# Robotics_Booster_Pack.net
KiCad netlist of a schematic drawn in EAGLE
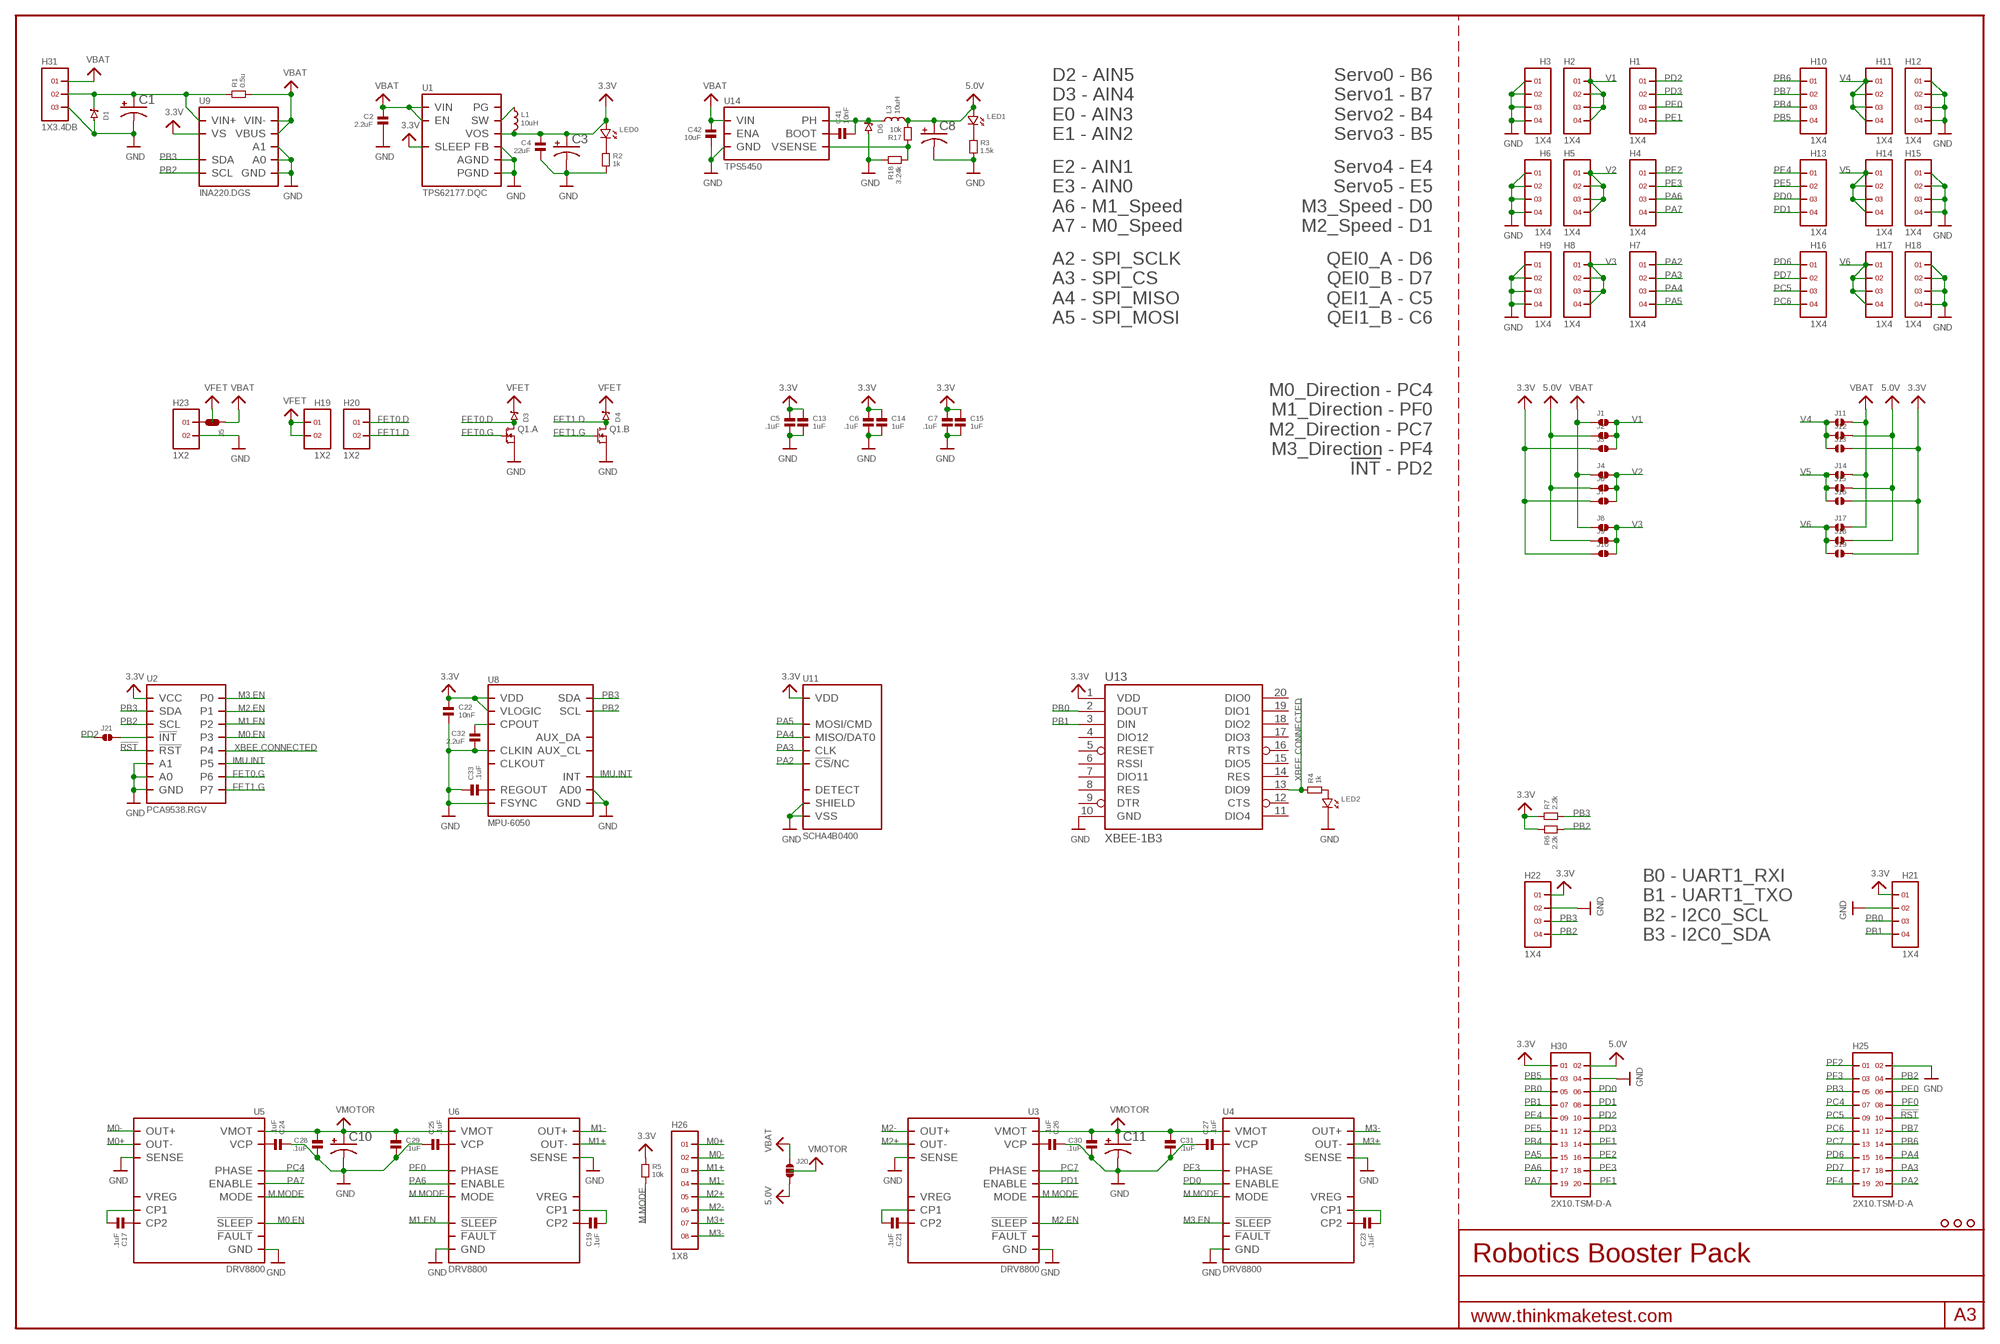
[diagram p0: schematic, sheet 1]

(export (version "E")
  (design (tool "Eeschema 10.0.6"))
  (components
    (comp (ref "C1")
      (value "CPOL-USE")
      (footprint "eagle-import:PANASONIC_E")
      (libsource (lib "eagle-import") (part "CPOL-USE"))
    )
    (comp (ref "C2")
      (value "2.2uF")
      (footprint "eagle-import:0603")
      (libsource (lib "eagle-import") (part "CAPACITOR.0603"))
    )
    (comp (ref "C3")
      (value "CPOL-USE")
      (footprint "eagle-import:PANASONIC_E")
      (libsource (lib "eagle-import") (part "CPOL-USE"))
    )
    (comp (ref "C4")
      (value "22uF")
      (footprint "eagle-import:0805")
      (libsource (lib "eagle-import") (part "CAPACITOR.0805"))
    )
    (comp (ref "C5")
      (value ".1uF")
      (footprint "eagle-import:0603")
      (libsource (lib "eagle-import") (part "CAPACITOR.0603"))
    )
    (comp (ref "C6")
      (value ".1uF")
      (footprint "eagle-import:0603")
      (libsource (lib "eagle-import") (part "CAPACITOR.0603"))
    )
    (comp (ref "C7")
      (value ".1uF")
      (footprint "eagle-import:0603")
      (libsource (lib "eagle-import") (part "CAPACITOR.0603"))
    )
    (comp (ref "C8")
      (value "CPOL-USE")
      (footprint "eagle-import:PANASONIC_E")
      (libsource (lib "eagle-import") (part "CPOL-USE"))
    )
    (comp (ref "C10")
      (value "CPOL-USE")
      (footprint "eagle-import:PANASONIC_E")
      (libsource (lib "eagle-import") (part "CPOL-USE"))
    )
    (comp (ref "C11")
      (value "CPOL-USE")
      (footprint "eagle-import:PANASONIC_E")
      (libsource (lib "eagle-import") (part "CPOL-USE"))
    )
    (comp (ref "C13")
      (value "1uF")
      (footprint "eagle-import:0603")
      (libsource (lib "eagle-import") (part "CAPACITOR.0603"))
    )
    (comp (ref "C14")
      (value "1uF")
      (footprint "eagle-import:0603")
      (libsource (lib "eagle-import") (part "CAPACITOR.0603"))
    )
    (comp (ref "C15")
      (value "1uF")
      (footprint "eagle-import:0603")
      (libsource (lib "eagle-import") (part "CAPACITOR.0603"))
    )
    (comp (ref "C17")
      (value ".1uF")
      (footprint "eagle-import:0603")
      (libsource (lib "eagle-import") (part "CAPACITOR.0603"))
    )
    (comp (ref "C19")
      (value ".1uF")
      (footprint "eagle-import:0603")
      (libsource (lib "eagle-import") (part "CAPACITOR.0603"))
    )
    (comp (ref "C21")
      (value ".1uF")
      (footprint "eagle-import:0603")
      (libsource (lib "eagle-import") (part "CAPACITOR.0603"))
    )
    (comp (ref "C22")
      (value "10nF")
      (footprint "eagle-import:0603")
      (libsource (lib "eagle-import") (part "CAPACITOR.0603"))
    )
    (comp (ref "C23")
      (value ".1uF")
      (footprint "eagle-import:0603")
      (libsource (lib "eagle-import") (part "CAPACITOR.0603"))
    )
    (comp (ref "C24")
      (value ".1uF")
      (footprint "eagle-import:0603")
      (libsource (lib "eagle-import") (part "CAPACITOR.0603"))
    )
    (comp (ref "C25")
      (value ".1uF")
      (footprint "eagle-import:0603")
      (libsource (lib "eagle-import") (part "CAPACITOR.0603"))
    )
    (comp (ref "C26")
      (value ".1uF")
      (footprint "eagle-import:0603")
      (libsource (lib "eagle-import") (part "CAPACITOR.0603"))
    )
    (comp (ref "C27")
      (value ".1uF")
      (footprint "eagle-import:0603")
      (libsource (lib "eagle-import") (part "CAPACITOR.0603"))
    )
    (comp (ref "C28")
      (value ".1uF")
      (footprint "eagle-import:0603")
      (libsource (lib "eagle-import") (part "CAPACITOR.0603"))
    )
    (comp (ref "C29")
      (value ".1uF")
      (footprint "eagle-import:0603")
      (libsource (lib "eagle-import") (part "CAPACITOR.0603"))
    )
    (comp (ref "C30")
      (value ".1uF")
      (footprint "eagle-import:0603")
      (libsource (lib "eagle-import") (part "CAPACITOR.0603"))
    )
    (comp (ref "C31")
      (value ".1uF")
      (footprint "eagle-import:0603")
      (libsource (lib "eagle-import") (part "CAPACITOR.0603"))
    )
    (comp (ref "C32")
      (value "2.2uF")
      (footprint "eagle-import:0603")
      (libsource (lib "eagle-import") (part "CAPACITOR.0603"))
    )
    (comp (ref "C33")
      (value ".1uF")
      (footprint "eagle-import:0603")
      (libsource (lib "eagle-import") (part "CAPACITOR.0603"))
    )
    (comp (ref "C41")
      (value "10nF")
      (footprint "eagle-import:0603")
      (libsource (lib "eagle-import") (part "CAPACITOR.0603"))
    )
    (comp (ref "C42")
      (value "10uF")
      (footprint "eagle-import:1206")
      (libsource (lib "eagle-import") (part "CAPACITOR.1206"))
    )
    (comp (ref "D1")
      (value "CDBMT2100-HF")
      (footprint "eagle-import:SOD-123H")
      (libsource (lib "eagle-import") (part "CDBMT____-HF"))
    )
    (comp (ref "D3")
      (value "CDBMT2100-HF")
      (footprint "eagle-import:SOD-123H")
      (libsource (lib "eagle-import") (part "CDBMT____-HF"))
    )
    (comp (ref "D4")
      (value "CDBMT2100-HF")
      (footprint "eagle-import:SOD-123H")
      (libsource (lib "eagle-import") (part "CDBMT____-HF"))
    )
    (comp (ref "D6")
      (value "CDBC5XXX-G")
      (footprint "eagle-import:DO-214AB")
      (libsource (lib "eagle-import") (part "CDBC5XXX-G"))
    )
    (comp (ref "H1")
      (value "1X4")
      (footprint "eagle-import:1X4")
      (libsource (lib "eagle-import") (part "1X4"))
    )
    (comp (ref "H2")
      (value "1X4")
      (footprint "eagle-import:1X4")
      (libsource (lib "eagle-import") (part "1X4"))
    )
    (comp (ref "H3")
      (value "1X4")
      (footprint "eagle-import:1X4")
      (libsource (lib "eagle-import") (part "1X4"))
    )
    (comp (ref "H4")
      (value "1X4")
      (footprint "eagle-import:1X4")
      (libsource (lib "eagle-import") (part "1X4"))
    )
    (comp (ref "H5")
      (value "1X4")
      (footprint "eagle-import:1X4")
      (libsource (lib "eagle-import") (part "1X4"))
    )
    (comp (ref "H6")
      (value "1X4")
      (footprint "eagle-import:1X4")
      (libsource (lib "eagle-import") (part "1X4"))
    )
    (comp (ref "H7")
      (value "1X4")
      (footprint "eagle-import:1X4")
      (libsource (lib "eagle-import") (part "1X4"))
    )
    (comp (ref "H8")
      (value "1X4")
      (footprint "eagle-import:1X4")
      (libsource (lib "eagle-import") (part "1X4"))
    )
    (comp (ref "H9")
      (value "1X4")
      (footprint "eagle-import:1X4")
      (libsource (lib "eagle-import") (part "1X4"))
    )
    (comp (ref "H10")
      (value "1X4")
      (footprint "eagle-import:1X4")
      (libsource (lib "eagle-import") (part "1X4"))
    )
    (comp (ref "H11")
      (value "1X4")
      (footprint "eagle-import:1X4")
      (libsource (lib "eagle-import") (part "1X4"))
    )
    (comp (ref "H12")
      (value "1X4")
      (footprint "eagle-import:1X4")
      (libsource (lib "eagle-import") (part "1X4"))
    )
    (comp (ref "H13")
      (value "1X4")
      (footprint "eagle-import:1X4")
      (libsource (lib "eagle-import") (part "1X4"))
    )
    (comp (ref "H14")
      (value "1X4")
      (footprint "eagle-import:1X4")
      (libsource (lib "eagle-import") (part "1X4"))
    )
    (comp (ref "H15")
      (value "1X4")
      (footprint "eagle-import:1X4")
      (libsource (lib "eagle-import") (part "1X4"))
    )
    (comp (ref "H16")
      (value "1X4")
      (footprint "eagle-import:1X4")
      (libsource (lib "eagle-import") (part "1X4"))
    )
    (comp (ref "H17")
      (value "1X4")
      (footprint "eagle-import:1X4")
      (libsource (lib "eagle-import") (part "1X4"))
    )
    (comp (ref "H18")
      (value "1X4")
      (footprint "eagle-import:1X4")
      (libsource (lib "eagle-import") (part "1X4"))
    )
    (comp (ref "H19")
      (value "1X2")
      (footprint "eagle-import:1X2")
      (libsource (lib "eagle-import") (part "1X2"))
    )
    (comp (ref "H20")
      (value "1X2")
      (footprint "eagle-import:1X2")
      (libsource (lib "eagle-import") (part "1X2"))
    )
    (comp (ref "H21")
      (value "1X4")
      (footprint "eagle-import:1X4")
      (libsource (lib "eagle-import") (part "1X4"))
    )
    (comp (ref "H22")
      (value "1X4")
      (footprint "eagle-import:1X4")
      (libsource (lib "eagle-import") (part "1X4"))
    )
    (comp (ref "H23")
      (value "1X2")
      (footprint "eagle-import:1X2")
      (libsource (lib "eagle-import") (part "1X2"))
    )
    (comp (ref "H25")
      (value "2X10.TSM-D-A")
      (footprint "eagle-import:TSM-110-XX-XXX-DV-A")
      (libsource (lib "eagle-import") (part "2X10.TSM-D-A"))
    )
    (comp (ref "H26")
      (value "1X8")
      (footprint "eagle-import:1824480000")
      (libsource (lib "eagle-import") (part "1X8"))
    )
    (comp (ref "H30")
      (value "2X10.TSM-D-A")
      (footprint "eagle-import:TSM-110-XX-XXX-DV-A")
      (libsource (lib "eagle-import") (part "2X10.TSM-D-A"))
    )
    (comp (ref "H31")
      (value "1X3.4DB")
      (footprint "eagle-import:4DB-P108-02")
      (libsource (lib "eagle-import") (part "1X3.4DB"))
    )
    (comp (ref "J1")
      (value "SOLDERJUMPER.2.LRG")
      (footprint "eagle-import:2.LRG")
      (libsource (lib "eagle-import") (part "SOLDERJUMPER.2.LRG"))
    )
    (comp (ref "J2")
      (value "SOLDERJUMPER.2.LRG")
      (footprint "eagle-import:2.LRG")
      (libsource (lib "eagle-import") (part "SOLDERJUMPER.2.LRG"))
    )
    (comp (ref "J3")
      (value "SOLDERJUMPER.2.LRG.PASTE")
      (footprint "eagle-import:2.LRG.PASTE")
      (libsource (lib "eagle-import") (part "SOLDERJUMPER.2.LRG.PASTE"))
    )
    (comp (ref "J4")
      (value "SOLDERJUMPER.2.LRG")
      (footprint "eagle-import:2.LRG")
      (libsource (lib "eagle-import") (part "SOLDERJUMPER.2.LRG"))
    )
    (comp (ref "J5")
      (value "SOLDERJUMPER.3.LRG.12")
      (footprint "eagle-import:3.LRG.12")
      (libsource (lib "eagle-import") (part "SOLDERJUMPER.3.LRG.12"))
    )
    (comp (ref "J6")
      (value "SOLDERJUMPER.2.LRG")
      (footprint "eagle-import:2.LRG")
      (libsource (lib "eagle-import") (part "SOLDERJUMPER.2.LRG"))
    )
    (comp (ref "J7")
      (value "SOLDERJUMPER.2.LRG.PASTE")
      (footprint "eagle-import:2.LRG.PASTE")
      (libsource (lib "eagle-import") (part "SOLDERJUMPER.2.LRG.PASTE"))
    )
    (comp (ref "J8")
      (value "SOLDERJUMPER.2.LRG")
      (footprint "eagle-import:2.LRG")
      (libsource (lib "eagle-import") (part "SOLDERJUMPER.2.LRG"))
    )
    (comp (ref "J9")
      (value "SOLDERJUMPER.2.LRG")
      (footprint "eagle-import:2.LRG")
      (libsource (lib "eagle-import") (part "SOLDERJUMPER.2.LRG"))
    )
    (comp (ref "J10")
      (value "SOLDERJUMPER.2.LRG.PASTE")
      (footprint "eagle-import:2.LRG.PASTE")
      (libsource (lib "eagle-import") (part "SOLDERJUMPER.2.LRG.PASTE"))
    )
    (comp (ref "J11")
      (value "SOLDERJUMPER.2.LRG")
      (footprint "eagle-import:2.LRG")
      (libsource (lib "eagle-import") (part "SOLDERJUMPER.2.LRG"))
    )
    (comp (ref "J12")
      (value "SOLDERJUMPER.2.LRG.PASTE")
      (footprint "eagle-import:2.LRG.PASTE")
      (libsource (lib "eagle-import") (part "SOLDERJUMPER.2.LRG.PASTE"))
    )
    (comp (ref "J13")
      (value "SOLDERJUMPER.2.LRG")
      (footprint "eagle-import:2.LRG")
      (libsource (lib "eagle-import") (part "SOLDERJUMPER.2.LRG"))
    )
    (comp (ref "J14")
      (value "SOLDERJUMPER.2.LRG")
      (footprint "eagle-import:2.LRG")
      (libsource (lib "eagle-import") (part "SOLDERJUMPER.2.LRG"))
    )
    (comp (ref "J15")
      (value "SOLDERJUMPER.2.LRG")
      (footprint "eagle-import:2.LRG")
      (libsource (lib "eagle-import") (part "SOLDERJUMPER.2.LRG"))
    )
    (comp (ref "J16")
      (value "SOLDERJUMPER.2.LRG.PASTE")
      (footprint "eagle-import:2.LRG.PASTE")
      (libsource (lib "eagle-import") (part "SOLDERJUMPER.2.LRG.PASTE"))
    )
    (comp (ref "J17")
      (value "SOLDERJUMPER.2.LRG")
      (footprint "eagle-import:2.LRG")
      (libsource (lib "eagle-import") (part "SOLDERJUMPER.2.LRG"))
    )
    (comp (ref "J18")
      (value "SOLDERJUMPER.2.LRG")
      (footprint "eagle-import:2.LRG")
      (libsource (lib "eagle-import") (part "SOLDERJUMPER.2.LRG"))
    )
    (comp (ref "J19")
      (value "SOLDERJUMPER.2.LRG.PASTE")
      (footprint "eagle-import:2.LRG.PASTE")
      (libsource (lib "eagle-import") (part "SOLDERJUMPER.2.LRG.PASTE"))
    )
    (comp (ref "J20")
      (value "SOLDERJUMPER.3.LRG.12")
      (footprint "eagle-import:3.LRG.12")
      (libsource (lib "eagle-import") (part "SOLDERJUMPER.3.LRG.12"))
    )
    (comp (ref "J21")
      (value "SOLDERJUMPER.2.LRG")
      (footprint "eagle-import:2.LRG")
      (libsource (lib "eagle-import") (part "SOLDERJUMPER.2.LRG"))
    )
    (comp (ref "L1")
      (value "10uH")
      (footprint "eagle-import:SRN6045")
      (libsource (lib "eagle-import") (part "INDUCTOR-SRN6045"))
    )
    (comp (ref "L3")
      (value "10uH")
      (footprint "eagle-import:XAL6060")
      (libsource (lib "eagle-import") (part "INDUCTOR.XAL6060"))
    )
    (comp (ref "LED0")
      (value "LED.0603")
      (footprint "eagle-import:0603.LED")
      (libsource (lib "eagle-import") (part "LED.0603"))
    )
    (comp (ref "LED1")
      (value "LED.0603")
      (footprint "eagle-import:0603.LED")
      (libsource (lib "eagle-import") (part "LED.0603"))
    )
    (comp (ref "LED2")
      (value "LED.0603")
      (footprint "eagle-import:0603.LED")
      (libsource (lib "eagle-import") (part "LED.0603"))
    )
    (comp (ref "Q1")
      (value "FDMA")
      (footprint "eagle-import:MICROFET.2X2")
      (libsource (lib "eagle-import") (part "FDMA"))
    )
    (comp (ref "R1")
      (value "0.5u")
      (footprint "eagle-import:2512")
      (libsource (lib "eagle-import") (part "RESISTOR.2512"))
    )
    (comp (ref "R2")
      (value "1k")
      (footprint "eagle-import:0603")
      (libsource (lib "eagle-import") (part "RESISTOR.0603"))
    )
    (comp (ref "R3")
      (value "1.5k")
      (footprint "eagle-import:0603")
      (libsource (lib "eagle-import") (part "RESISTOR.0603"))
    )
    (comp (ref "R4")
      (value "1k")
      (footprint "eagle-import:0603")
      (libsource (lib "eagle-import") (part "RESISTOR.0603"))
    )
    (comp (ref "R5")
      (value "10k")
      (footprint "eagle-import:0603")
      (libsource (lib "eagle-import") (part "RESISTOR.0603"))
    )
    (comp (ref "R6")
      (value "2.2k")
      (footprint "eagle-import:0603")
      (libsource (lib "eagle-import") (part "RESISTOR.0603"))
    )
    (comp (ref "R7")
      (value "2.2k")
      (footprint "eagle-import:0603")
      (libsource (lib "eagle-import") (part "RESISTOR.0603"))
    )
    (comp (ref "R17")
      (value "10k")
      (footprint "eagle-import:0603")
      (libsource (lib "eagle-import") (part "RESISTOR.0603"))
    )
    (comp (ref "R18")
      (value "3.24k")
      (footprint "eagle-import:0603")
      (libsource (lib "eagle-import") (part "RESISTOR.0603"))
    )
    (comp (ref "U$3")
      (value "HOLE.4MM")
      (footprint "eagle-import:#4")
      (libsource (lib "eagle-import") (part "HOLE.4MM"))
    )
    (comp (ref "U$4")
      (value "HOLE.4MM")
      (footprint "eagle-import:#4")
      (libsource (lib "eagle-import") (part "HOLE.4MM"))
    )
    (comp (ref "U$21")
      (value "HOLE.4MM")
      (footprint "eagle-import:#4")
      (libsource (lib "eagle-import") (part "HOLE.4MM"))
    )
    (comp (ref "U1")
      (value "TPS62177.DQC")
      (footprint "eagle-import:DQC")
      (libsource (lib "eagle-import") (part "TPS62177.DQC"))
    )
    (comp (ref "U2")
      (value "PCA9538.RGV")
      (footprint "eagle-import:RGV.16")
      (libsource (lib "eagle-import") (part "PCA9538.RGV"))
    )
    (comp (ref "U3")
      (value "DRV8800")
      (footprint "eagle-import:RTY.16")
      (libsource (lib "eagle-import") (part "DRV8800.RTY"))
    )
    (comp (ref "U4")
      (value "DRV8800")
      (footprint "eagle-import:RTY.16")
      (libsource (lib "eagle-import") (part "DRV8800.RTY"))
    )
    (comp (ref "U5")
      (value "DRV8800")
      (footprint "eagle-import:RTY.16")
      (libsource (lib "eagle-import") (part "DRV8800.RTY"))
    )
    (comp (ref "U6")
      (value "DRV8800")
      (footprint "eagle-import:RTY.16")
      (libsource (lib "eagle-import") (part "DRV8800.RTY"))
    )
    (comp (ref "U8")
      (value "MPU-6050")
      (footprint "eagle-import:QFN.24.4X4")
      (libsource (lib "eagle-import") (part "MPU-6050"))
    )
    (comp (ref "U9")
      (value "INA220.DGS")
      (footprint "eagle-import:DGS.10")
      (libsource (lib "eagle-import") (part "INA220.DGS"))
    )
    (comp (ref "U11")
      (value "SCHA4B0400")
      (footprint "eagle-import:SCHA4B0400")
      (libsource (lib "eagle-import") (part "SCHA4B0400"))
    )
    (comp (ref "U13")
      (value "XBEE-1B3")
      (footprint "eagle-import:XBEE-SMD")
      (libsource (lib "eagle-import") (part "XBEE-1B3"))
    )
    (comp (ref "U14")
      (value "TPS5450")
      (footprint "eagle-import:DDA")
      (libsource (lib "eagle-import") (part "TPS54X0"))
    )
  )
  (nets
    (net (code "1") (name "/FET0.D") (class "Default")
      (node (ref "D3") (pin "2") (pinfunction "2_2") (pintype "bidirectional"))
      (node (ref "H20") (pin "1") (pinfunction "1_1") (pintype "bidirectional"))
      (node (ref "Q1") (pin "6") (pinfunction "D_6") (pintype "bidirectional"))
      (node (ref "Q1") (pin "PAD@1") (pinfunction "D_PAD@1") (pintype "bidirectional"))
    )
    (net (code "2") (name "/FET0.G") (class "Default")
      (node (ref "Q1") (pin "2") (pinfunction "G_2") (pintype "bidirectional"))
      (node (ref "U2") (pin "9") (pinfunction "P6_9") (pintype "bidirectional"))
    )
    (net (code "3") (name "/FET1.D") (class "Default")
      (node (ref "D4") (pin "2") (pinfunction "2_2") (pintype "bidirectional"))
      (node (ref "H20") (pin "2") (pinfunction "2_2") (pintype "bidirectional"))
      (node (ref "Q1") (pin "3") (pinfunction "D_3") (pintype "bidirectional"))
      (node (ref "Q1") (pin "PAD@2") (pinfunction "D_PAD@2") (pintype "bidirectional"))
    )
    (net (code "4") (name "/FET1.G") (class "Default")
      (node (ref "Q1") (pin "5") (pinfunction "G_5") (pintype "bidirectional"))
      (node (ref "U2") (pin "10") (pinfunction "P7_10") (pintype "bidirectional"))
    )
    (net (code "5") (name "/IMU.INT") (class "Default")
      (node (ref "U2") (pin "8") (pinfunction "P5_8") (pintype "bidirectional"))
      (node (ref "U8") (pin "12") (pinfunction "INT_12") (pintype "bidirectional"))
    )
    (net (code "6") (name "/M.MODE") (class "Default")
      (node (ref "R5") (pin "2") (pinfunction "2_2") (pintype "bidirectional"))
      (node (ref "U3") (pin "16") (pinfunction "MODE_16") (pintype "bidirectional"))
      (node (ref "U4") (pin "16") (pinfunction "MODE_16") (pintype "bidirectional"))
      (node (ref "U5") (pin "16") (pinfunction "MODE_16") (pintype "bidirectional"))
      (node (ref "U6") (pin "16") (pinfunction "MODE_16") (pintype "bidirectional"))
    )
    (net (code "7") (name "/M0+") (class "Default")
      (node (ref "H26") (pin "1@1") (pinfunction "1_1@1") (pintype "bidirectional"))
      (node (ref "H26") (pin "1@2") (pinfunction "1_1@2") (pintype "bidirectional"))
      (node (ref "U5") (pin "9") (pinfunction "OUT-_9") (pintype "bidirectional"))
    )
    (net (code "8") (name "/M0-") (class "Default")
      (node (ref "H26") (pin "2@1") (pinfunction "2_2@1") (pintype "bidirectional"))
      (node (ref "H26") (pin "2@2") (pinfunction "2_2@2") (pintype "bidirectional"))
      (node (ref "U5") (pin "6") (pinfunction "OUT+_6") (pintype "bidirectional"))
    )
    (net (code "9") (name "/M0.EN") (class "Default")
      (node (ref "U2") (pin "5") (pinfunction "P3_5") (pintype "bidirectional"))
      (node (ref "U5") (pin "3") (pinfunction "~{SLEEP}_3") (pintype "bidirectional"))
    )
    (net (code "10") (name "/M1+") (class "Default")
      (node (ref "H26") (pin "3@1") (pinfunction "3_3@1") (pintype "bidirectional"))
      (node (ref "H26") (pin "3@2") (pinfunction "3_3@2") (pintype "bidirectional"))
      (node (ref "U6") (pin "9") (pinfunction "OUT-_9") (pintype "bidirectional"))
    )
    (net (code "11") (name "/M1-") (class "Default")
      (node (ref "H26") (pin "4@1") (pinfunction "4_4@1") (pintype "bidirectional"))
      (node (ref "H26") (pin "4@2") (pinfunction "4_4@2") (pintype "bidirectional"))
      (node (ref "U6") (pin "6") (pinfunction "OUT+_6") (pintype "bidirectional"))
    )
    (net (code "12") (name "/M1.EN") (class "Default")
      (node (ref "U2") (pin "4") (pinfunction "P2_4") (pintype "bidirectional"))
      (node (ref "U6") (pin "3") (pinfunction "~{SLEEP}_3") (pintype "bidirectional"))
    )
    (net (code "13") (name "/M2+") (class "Default")
      (node (ref "H26") (pin "5@1") (pinfunction "5_5@1") (pintype "bidirectional"))
      (node (ref "H26") (pin "5@2") (pinfunction "5_5@2") (pintype "bidirectional"))
      (node (ref "U3") (pin "9") (pinfunction "OUT-_9") (pintype "bidirectional"))
    )
    (net (code "14") (name "/M2-") (class "Default")
      (node (ref "H26") (pin "6@1") (pinfunction "6_6@1") (pintype "bidirectional"))
      (node (ref "H26") (pin "6@2") (pinfunction "6_6@2") (pintype "bidirectional"))
      (node (ref "U3") (pin "6") (pinfunction "OUT+_6") (pintype "bidirectional"))
    )
    (net (code "15") (name "/M2.EN") (class "Default")
      (node (ref "U2") (pin "3") (pinfunction "P1_3") (pintype "bidirectional"))
      (node (ref "U3") (pin "3") (pinfunction "~{SLEEP}_3") (pintype "bidirectional"))
    )
    (net (code "16") (name "/M3+") (class "Default")
      (node (ref "H26") (pin "7@1") (pinfunction "7_7@1") (pintype "bidirectional"))
      (node (ref "H26") (pin "7@2") (pinfunction "7_7@2") (pintype "bidirectional"))
      (node (ref "U4") (pin "9") (pinfunction "OUT-_9") (pintype "bidirectional"))
    )
    (net (code "17") (name "/M3-") (class "Default")
      (node (ref "H26") (pin "8@1") (pinfunction "8_8@1") (pintype "bidirectional"))
      (node (ref "H26") (pin "8@2") (pinfunction "8_8@2") (pintype "bidirectional"))
      (node (ref "U4") (pin "6") (pinfunction "OUT+_6") (pintype "bidirectional"))
    )
    (net (code "18") (name "/M3.EN") (class "Default")
      (node (ref "U2") (pin "2") (pinfunction "P0_2") (pintype "bidirectional"))
      (node (ref "U4") (pin "3") (pinfunction "~{SLEEP}_3") (pintype "bidirectional"))
    )
    (net (code "19") (name "/PA2") (class "Default")
      (node (ref "H25") (pin "20") (pinfunction "20_20") (pintype "bidirectional"))
      (node (ref "H7") (pin "1") (pinfunction "1_1") (pintype "bidirectional"))
      (node (ref "U11") (pin "!CS!/NC/DAT3") (pinfunction "~{CS}/NC_!CS!/NC/DAT3") (pintype "bidirectional"))
    )
    (net (code "20") (name "/PA3") (class "Default")
      (node (ref "H25") (pin "18") (pinfunction "18_18") (pintype "bidirectional"))
      (node (ref "H7") (pin "2") (pinfunction "2_2") (pintype "bidirectional"))
      (node (ref "U11") (pin "CLK") (pinfunction "CLK_CLK") (pintype "bidirectional"))
    )
    (net (code "21") (name "/PA4") (class "Default")
      (node (ref "H25") (pin "16") (pinfunction "16_16") (pintype "bidirectional"))
      (node (ref "H7") (pin "3") (pinfunction "3_3") (pintype "bidirectional"))
      (node (ref "U11") (pin "MISO/DAT0") (pinfunction "MISO/DAT0_MISO/DAT0") (pintype "bidirectional"))
    )
    (net (code "22") (name "/PA5") (class "Default")
      (node (ref "H30") (pin "15") (pinfunction "15_15") (pintype "bidirectional"))
      (node (ref "H7") (pin "4") (pinfunction "4_4") (pintype "bidirectional"))
      (node (ref "U11") (pin "MOSI/CMD") (pinfunction "MOSI/CMD_MOSI/CMD") (pintype "bidirectional"))
    )
    (net (code "23") (name "/PA6") (class "Default")
      (node (ref "H30") (pin "17") (pinfunction "17_17") (pintype "bidirectional"))
      (node (ref "H4") (pin "3") (pinfunction "3_3") (pintype "bidirectional"))
      (node (ref "U6") (pin "4") (pinfunction "ENABLE_4") (pintype "bidirectional"))
    )
    (net (code "24") (name "/PA7") (class "Default")
      (node (ref "H30") (pin "19") (pinfunction "19_19") (pintype "bidirectional"))
      (node (ref "H4") (pin "4") (pinfunction "4_4") (pintype "bidirectional"))
      (node (ref "U5") (pin "4") (pinfunction "ENABLE_4") (pintype "bidirectional"))
    )
    (net (code "25") (name "/PB0") (class "Default")
      (node (ref "H21") (pin "3") (pinfunction "3_3") (pintype "bidirectional"))
      (node (ref "H30") (pin "5") (pinfunction "5_5") (pintype "bidirectional"))
      (node (ref "U13") (pin "2") (pinfunction "DOUT_2") (pintype "output"))
    )
    (net (code "26") (name "/PB1") (class "Default")
      (node (ref "H21") (pin "4") (pinfunction "4_4") (pintype "bidirectional"))
      (node (ref "H30") (pin "7") (pinfunction "7_7") (pintype "bidirectional"))
      (node (ref "U13") (pin "3") (pinfunction "DIN_3") (pintype "input"))
    )
    (net (code "27") (name "/PB2") (class "Default")
      (node (ref "H22") (pin "4") (pinfunction "4_4") (pintype "bidirectional"))
      (node (ref "H25") (pin "4") (pinfunction "4_4") (pintype "bidirectional"))
      (node (ref "R6") (pin "2") (pinfunction "2_2") (pintype "bidirectional"))
      (node (ref "U2") (pin "12") (pinfunction "SCL_12") (pintype "bidirectional"))
      (node (ref "U8") (pin "23") (pinfunction "SCL_23") (pintype "bidirectional"))
      (node (ref "U9") (pin "5") (pinfunction "SCL_5") (pintype "bidirectional"))
    )
    (net (code "28") (name "/PB3") (class "Default")
      (node (ref "H22") (pin "3") (pinfunction "3_3") (pintype "bidirectional"))
      (node (ref "H25") (pin "5") (pinfunction "5_5") (pintype "bidirectional"))
      (node (ref "R7") (pin "2") (pinfunction "2_2") (pintype "bidirectional"))
      (node (ref "U2") (pin "13") (pinfunction "SDA_13") (pintype "bidirectional"))
      (node (ref "U8") (pin "24") (pinfunction "SDA_24") (pintype "bidirectional"))
      (node (ref "U9") (pin "4") (pinfunction "SDA_4") (pintype "bidirectional"))
    )
    (net (code "29") (name "/PB4") (class "Default")
      (node (ref "H10") (pin "3") (pinfunction "3_3") (pintype "bidirectional"))
      (node (ref "H30") (pin "13") (pinfunction "13_13") (pintype "bidirectional"))
    )
    (net (code "30") (name "/PB5") (class "Default")
      (node (ref "H10") (pin "4") (pinfunction "4_4") (pintype "bidirectional"))
      (node (ref "H30") (pin "3") (pinfunction "3_3") (pintype "bidirectional"))
    )
    (net (code "31") (name "/PB6") (class "Default")
      (node (ref "H10") (pin "1") (pinfunction "1_1") (pintype "bidirectional"))
      (node (ref "H25") (pin "14") (pinfunction "14_14") (pintype "bidirectional"))
    )
    (net (code "32") (name "/PB7") (class "Default")
      (node (ref "H10") (pin "2") (pinfunction "2_2") (pintype "bidirectional"))
      (node (ref "H25") (pin "12") (pinfunction "12_12") (pintype "bidirectional"))
    )
    (net (code "33") (name "/PC4") (class "Default")
      (node (ref "H25") (pin "7") (pinfunction "7_7") (pintype "bidirectional"))
      (node (ref "U5") (pin "1") (pinfunction "PHASE_1") (pintype "bidirectional"))
    )
    (net (code "34") (name "/PC5") (class "Default")
      (node (ref "H16") (pin "3") (pinfunction "3_3") (pintype "bidirectional"))
      (node (ref "H25") (pin "9") (pinfunction "9_9") (pintype "bidirectional"))
    )
    (net (code "35") (name "/PC6") (class "Default")
      (node (ref "H16") (pin "4") (pinfunction "4_4") (pintype "bidirectional"))
      (node (ref "H25") (pin "11") (pinfunction "11_11") (pintype "bidirectional"))
    )
    (net (code "36") (name "/PC7") (class "Default")
      (node (ref "H25") (pin "13") (pinfunction "13_13") (pintype "bidirectional"))
      (node (ref "U3") (pin "1") (pinfunction "PHASE_1") (pintype "bidirectional"))
    )
    (net (code "37") (name "/PD0") (class "Default")
      (node (ref "H13") (pin "3") (pinfunction "3_3") (pintype "bidirectional"))
      (node (ref "H30") (pin "6") (pinfunction "6_6") (pintype "bidirectional"))
      (node (ref "U4") (pin "4") (pinfunction "ENABLE_4") (pintype "bidirectional"))
    )
    (net (code "38") (name "/PD1") (class "Default")
      (node (ref "H13") (pin "4") (pinfunction "4_4") (pintype "bidirectional"))
      (node (ref "H30") (pin "8") (pinfunction "8_8") (pintype "bidirectional"))
      (node (ref "U3") (pin "4") (pinfunction "ENABLE_4") (pintype "bidirectional"))
    )
    (net (code "39") (name "/PD2") (class "Default")
      (node (ref "H1") (pin "1") (pinfunction "1_1") (pintype "bidirectional"))
      (node (ref "H30") (pin "10") (pinfunction "10_10") (pintype "bidirectional"))
      (node (ref "J21") (pin "1") (pinfunction "1_1") (pintype "bidirectional"))
    )
    (net (code "40") (name "/PD3") (class "Default")
      (node (ref "H1") (pin "2") (pinfunction "2_2") (pintype "bidirectional"))
      (node (ref "H30") (pin "12") (pinfunction "12_12") (pintype "bidirectional"))
    )
    (net (code "41") (name "/PD6") (class "Default")
      (node (ref "H16") (pin "1") (pinfunction "1_1") (pintype "bidirectional"))
      (node (ref "H25") (pin "15") (pinfunction "15_15") (pintype "bidirectional"))
    )
    (net (code "42") (name "/PD7") (class "Default")
      (node (ref "H16") (pin "2") (pinfunction "2_2") (pintype "bidirectional"))
      (node (ref "H25") (pin "17") (pinfunction "17_17") (pintype "bidirectional"))
    )
    (net (code "43") (name "/PE0") (class "Default")
      (node (ref "H1") (pin "3") (pinfunction "3_3") (pintype "bidirectional"))
      (node (ref "H25") (pin "6") (pinfunction "6_6") (pintype "bidirectional"))
    )
    (net (code "44") (name "/PE1") (class "Default")
      (node (ref "H1") (pin "4") (pinfunction "4_4") (pintype "bidirectional"))
      (node (ref "H30") (pin "14") (pinfunction "14_14") (pintype "bidirectional"))
    )
    (net (code "45") (name "/PE2") (class "Default")
      (node (ref "H30") (pin "16") (pinfunction "16_16") (pintype "bidirectional"))
      (node (ref "H4") (pin "1") (pinfunction "1_1") (pintype "bidirectional"))
    )
    (net (code "46") (name "/PE3") (class "Default")
      (node (ref "H30") (pin "18") (pinfunction "18_18") (pintype "bidirectional"))
      (node (ref "H4") (pin "2") (pinfunction "2_2") (pintype "bidirectional"))
    )
    (net (code "47") (name "/PE4") (class "Default")
      (node (ref "H13") (pin "1") (pinfunction "1_1") (pintype "bidirectional"))
      (node (ref "H30") (pin "9") (pinfunction "9_9") (pintype "bidirectional"))
    )
    (net (code "48") (name "/PE5") (class "Default")
      (node (ref "H13") (pin "2") (pinfunction "2_2") (pintype "bidirectional"))
      (node (ref "H30") (pin "11") (pinfunction "11_11") (pintype "bidirectional"))
    )
    (net (code "49") (name "/PF0") (class "Default")
      (node (ref "H25") (pin "8") (pinfunction "8_8") (pintype "bidirectional"))
      (node (ref "U6") (pin "1") (pinfunction "PHASE_1") (pintype "bidirectional"))
    )
    (net (code "50") (name "/PF1") (class "Default")
      (node (ref "H30") (pin "20") (pinfunction "20_20") (pintype "bidirectional"))
    )
    (net (code "51") (name "/PF2") (class "Default")
      (node (ref "H25") (pin "1") (pinfunction "1_1") (pintype "bidirectional"))
    )
    (net (code "52") (name "/PF3") (class "Default")
      (node (ref "H25") (pin "3") (pinfunction "3_3") (pintype "bidirectional"))
      (node (ref "U4") (pin "1") (pinfunction "PHASE_1") (pintype "bidirectional"))
    )
    (net (code "53") (name "/PF4") (class "Default")
      (node (ref "H25") (pin "19") (pinfunction "19_19") (pintype "bidirectional"))
    )
    (net (code "54") (name "/V1") (class "Default")
      (node (ref "H2") (pin "1") (pinfunction "1_1") (pintype "bidirectional"))
      (node (ref "H2") (pin "2") (pinfunction "2_2") (pintype "bidirectional"))
      (node (ref "H2") (pin "3") (pinfunction "3_3") (pintype "bidirectional"))
      (node (ref "H2") (pin "4") (pinfunction "4_4") (pintype "bidirectional"))
      (node (ref "J1") (pin "2") (pinfunction "2_2") (pintype "bidirectional"))
      (node (ref "J2") (pin "2") (pinfunction "2_2") (pintype "bidirectional"))
      (node (ref "J3") (pin "2") (pinfunction "2_2") (pintype "bidirectional"))
    )
    (net (code "55") (name "/V2") (class "Default")
      (node (ref "H5") (pin "1") (pinfunction "1_1") (pintype "bidirectional"))
      (node (ref "H5") (pin "2") (pinfunction "2_2") (pintype "bidirectional"))
      (node (ref "H5") (pin "3") (pinfunction "3_3") (pintype "bidirectional"))
      (node (ref "H5") (pin "4") (pinfunction "4_4") (pintype "bidirectional"))
      (node (ref "J4") (pin "2") (pinfunction "2_2") (pintype "bidirectional"))
      (node (ref "J6") (pin "2") (pinfunction "2_2") (pintype "bidirectional"))
      (node (ref "J7") (pin "2") (pinfunction "2_2") (pintype "bidirectional"))
    )
    (net (code "56") (name "/V3") (class "Default")
      (node (ref "H8") (pin "1") (pinfunction "1_1") (pintype "bidirectional"))
      (node (ref "H8") (pin "2") (pinfunction "2_2") (pintype "bidirectional"))
      (node (ref "H8") (pin "3") (pinfunction "3_3") (pintype "bidirectional"))
      (node (ref "H8") (pin "4") (pinfunction "4_4") (pintype "bidirectional"))
      (node (ref "J10") (pin "2") (pinfunction "2_2") (pintype "bidirectional"))
      (node (ref "J8") (pin "2") (pinfunction "2_2") (pintype "bidirectional"))
      (node (ref "J9") (pin "2") (pinfunction "2_2") (pintype "bidirectional"))
    )
    (net (code "57") (name "/V4") (class "Default")
      (node (ref "H11") (pin "1") (pinfunction "1_1") (pintype "bidirectional"))
      (node (ref "H11") (pin "2") (pinfunction "2_2") (pintype "bidirectional"))
      (node (ref "H11") (pin "3") (pinfunction "3_3") (pintype "bidirectional"))
      (node (ref "H11") (pin "4") (pinfunction "4_4") (pintype "bidirectional"))
      (node (ref "J11") (pin "2") (pinfunction "2_2") (pintype "bidirectional"))
      (node (ref "J12") (pin "2") (pinfunction "2_2") (pintype "bidirectional"))
      (node (ref "J13") (pin "2") (pinfunction "2_2") (pintype "bidirectional"))
    )
    (net (code "58") (name "/V5") (class "Default")
      (node (ref "H14") (pin "1") (pinfunction "1_1") (pintype "bidirectional"))
      (node (ref "H14") (pin "2") (pinfunction "2_2") (pintype "bidirectional"))
      (node (ref "H14") (pin "3") (pinfunction "3_3") (pintype "bidirectional"))
      (node (ref "H14") (pin "4") (pinfunction "4_4") (pintype "bidirectional"))
      (node (ref "J14") (pin "2") (pinfunction "2_2") (pintype "bidirectional"))
      (node (ref "J15") (pin "2") (pinfunction "2_2") (pintype "bidirectional"))
      (node (ref "J16") (pin "2") (pinfunction "2_2") (pintype "bidirectional"))
    )
    (net (code "59") (name "/V6") (class "Default")
      (node (ref "H17") (pin "1") (pinfunction "1_1") (pintype "bidirectional"))
      (node (ref "H17") (pin "2") (pinfunction "2_2") (pintype "bidirectional"))
      (node (ref "H17") (pin "3") (pinfunction "3_3") (pintype "bidirectional"))
      (node (ref "H17") (pin "4") (pinfunction "4_4") (pintype "bidirectional"))
      (node (ref "J17") (pin "2") (pinfunction "2_2") (pintype "bidirectional"))
      (node (ref "J18") (pin "2") (pinfunction "2_2") (pintype "bidirectional"))
      (node (ref "J19") (pin "2") (pinfunction "2_2") (pintype "bidirectional"))
    )
    (net (code "60") (name "/XBEE.CONNECTED") (class "Default")
      (node (ref "R4") (pin "1") (pinfunction "1_1") (pintype "bidirectional"))
      (node (ref "U13") (pin "13") (pinfunction "DIO9_13") (pintype "bidirectional"))
      (node (ref "U2") (pin "7") (pinfunction "P4_7") (pintype "bidirectional"))
    )
    (net (code "61") (name "/~{RST}") (class "Default")
      (node (ref "H25") (pin "10") (pinfunction "10_10") (pintype "bidirectional"))
      (node (ref "U2") (pin "1") (pinfunction "~{RST}_1") (pintype "bidirectional"))
    )
    (net (code "62") (name "3.3V") (class "Default")
      (node (ref "C13") (pin "1") (pinfunction "1_1") (pintype "bidirectional"))
      (node (ref "C14") (pin "1") (pinfunction "1_1") (pintype "bidirectional"))
      (node (ref "C15") (pin "1") (pinfunction "1_1") (pintype "bidirectional"))
      (node (ref "C22") (pin "1") (pinfunction "1_1") (pintype "bidirectional"))
      (node (ref "C3") (pin "+") (pinfunction "+_+") (pintype "passive"))
      (node (ref "C4") (pin "1") (pinfunction "1_1") (pintype "bidirectional"))
      (node (ref "C5") (pin "1") (pinfunction "1_1") (pintype "bidirectional"))
      (node (ref "C6") (pin "1") (pinfunction "1_1") (pintype "bidirectional"))
      (node (ref "C7") (pin "1") (pinfunction "1_1") (pintype "bidirectional"))
      (node (ref "H21") (pin "1") (pinfunction "1_1") (pintype "bidirectional"))
      (node (ref "H22") (pin "1") (pinfunction "1_1") (pintype "bidirectional"))
      (node (ref "H30") (pin "1") (pinfunction "1_1") (pintype "bidirectional"))
      (node (ref "J10") (pin "1") (pinfunction "1_1") (pintype "bidirectional"))
      (node (ref "J13") (pin "1") (pinfunction "1_1") (pintype "bidirectional"))
      (node (ref "J16") (pin "1") (pinfunction "1_1") (pintype "bidirectional"))
      (node (ref "J19") (pin "1") (pinfunction "1_1") (pintype "bidirectional"))
      (node (ref "J3") (pin "1") (pinfunction "1_1") (pintype "bidirectional"))
      (node (ref "J7") (pin "1") (pinfunction "1_1") (pintype "bidirectional"))
      (node (ref "L1") (pin "2") (pinfunction "2_2") (pintype "passive"))
      (node (ref "LED0") (pin "P$1") (pinfunction "1_P$1") (pintype "bidirectional"))
      (node (ref "R5") (pin "1") (pinfunction "1_1") (pintype "bidirectional"))
      (node (ref "R6") (pin "1") (pinfunction "1_1") (pintype "bidirectional"))
      (node (ref "R7") (pin "1") (pinfunction "1_1") (pintype "bidirectional"))
      (node (ref "U1") (pin "10") (pinfunction "VOS_10") (pintype "bidirectional"))
      (node (ref "U1") (pin "8") (pinfunction "SLEEP_8") (pintype "bidirectional"))
      (node (ref "U11") (pin "VDD") (pinfunction "VDD_VDD") (pintype "bidirectional"))
      (node (ref "U13") (pin "1") (pinfunction "VDD_1") (pintype "power_in"))
      (node (ref "U2") (pin "14") (pinfunction "VCC_14") (pintype "bidirectional"))
      (node (ref "U8") (pin "13") (pinfunction "VDD_13") (pintype "bidirectional"))
      (node (ref "U8") (pin "8") (pinfunction "VLOGIC_8") (pintype "bidirectional"))
      (node (ref "U9") (pin "6") (pinfunction "VS_6") (pintype "bidirectional"))
    )
    (net (code "63") (name "5.0V") (class "Default")
      (node (ref "C8") (pin "+") (pinfunction "+_+") (pintype "passive"))
      (node (ref "H30") (pin "2") (pinfunction "2_2") (pintype "bidirectional"))
      (node (ref "J12") (pin "1") (pinfunction "1_1") (pintype "bidirectional"))
      (node (ref "J15") (pin "1") (pinfunction "1_1") (pintype "bidirectional"))
      (node (ref "J18") (pin "1") (pinfunction "1_1") (pintype "bidirectional"))
      (node (ref "J2") (pin "1") (pinfunction "1_1") (pintype "bidirectional"))
      (node (ref "J20") (pin "3") (pinfunction "3_3") (pintype "bidirectional"))
      (node (ref "J6") (pin "1") (pinfunction "1_1") (pintype "bidirectional"))
      (node (ref "J9") (pin "1") (pinfunction "1_1") (pintype "bidirectional"))
      (node (ref "L3") (pin "2") (pinfunction "2_2") (pintype "passive"))
      (node (ref "LED1") (pin "P$1") (pinfunction "1_P$1") (pintype "bidirectional"))
      (node (ref "R17") (pin "2") (pinfunction "2_2") (pintype "bidirectional"))
    )
    (net (code "64") (name "GND") (class "Default")
      (node (ref "C1") (pin "-") (pinfunction "-_-") (pintype "passive"))
      (node (ref "C10") (pin "-") (pinfunction "-_-") (pintype "passive"))
      (node (ref "C11") (pin "-") (pinfunction "-_-") (pintype "passive"))
      (node (ref "C13") (pin "2") (pinfunction "2_2") (pintype "bidirectional"))
      (node (ref "C14") (pin "2") (pinfunction "2_2") (pintype "bidirectional"))
      (node (ref "C15") (pin "2") (pinfunction "2_2") (pintype "bidirectional"))
      (node (ref "C2") (pin "2") (pinfunction "2_2") (pintype "bidirectional"))
      (node (ref "C22") (pin "2") (pinfunction "2_2") (pintype "bidirectional"))
      (node (ref "C24") (pin "1") (pinfunction "1_1") (pintype "bidirectional"))
      (node (ref "C25") (pin "1") (pinfunction "1_1") (pintype "bidirectional"))
      (node (ref "C26") (pin "1") (pinfunction "1_1") (pintype "bidirectional"))
      (node (ref "C27") (pin "1") (pinfunction "1_1") (pintype "bidirectional"))
      (node (ref "C28") (pin "2") (pinfunction "2_2") (pintype "bidirectional"))
      (node (ref "C29") (pin "2") (pinfunction "2_2") (pintype "bidirectional"))
      (node (ref "C3") (pin "-") (pinfunction "-_-") (pintype "passive"))
      (node (ref "C30") (pin "2") (pinfunction "2_2") (pintype "bidirectional"))
      (node (ref "C31") (pin "2") (pinfunction "2_2") (pintype "bidirectional"))
      (node (ref "C32") (pin "2") (pinfunction "2_2") (pintype "bidirectional"))
      (node (ref "C33") (pin "1") (pinfunction "1_1") (pintype "bidirectional"))
      (node (ref "C4") (pin "2") (pinfunction "2_2") (pintype "bidirectional"))
      (node (ref "C42") (pin "2") (pinfunction "2_2") (pintype "bidirectional"))
      (node (ref "C5") (pin "2") (pinfunction "2_2") (pintype "bidirectional"))
      (node (ref "C6") (pin "2") (pinfunction "2_2") (pintype "bidirectional"))
      (node (ref "C7") (pin "2") (pinfunction "2_2") (pintype "bidirectional"))
      (node (ref "C8") (pin "-") (pinfunction "-_-") (pintype "passive"))
      (node (ref "D1") (pin "2") (pinfunction "2_2") (pintype "bidirectional"))
      (node (ref "D6") (pin "2") (pinfunction "2_2") (pintype "bidirectional"))
      (node (ref "H12") (pin "1") (pinfunction "1_1") (pintype "bidirectional"))
      (node (ref "H12") (pin "2") (pinfunction "2_2") (pintype "bidirectional"))
      (node (ref "H12") (pin "3") (pinfunction "3_3") (pintype "bidirectional"))
      (node (ref "H12") (pin "4") (pinfunction "4_4") (pintype "bidirectional"))
      (node (ref "H15") (pin "1") (pinfunction "1_1") (pintype "bidirectional"))
      (node (ref "H15") (pin "2") (pinfunction "2_2") (pintype "bidirectional"))
      (node (ref "H15") (pin "3") (pinfunction "3_3") (pintype "bidirectional"))
      (node (ref "H15") (pin "4") (pinfunction "4_4") (pintype "bidirectional"))
      (node (ref "H18") (pin "1") (pinfunction "1_1") (pintype "bidirectional"))
      (node (ref "H18") (pin "2") (pinfunction "2_2") (pintype "bidirectional"))
      (node (ref "H18") (pin "3") (pinfunction "3_3") (pintype "bidirectional"))
      (node (ref "H18") (pin "4") (pinfunction "4_4") (pintype "bidirectional"))
      (node (ref "H21") (pin "2") (pinfunction "2_2") (pintype "bidirectional"))
      (node (ref "H22") (pin "2") (pinfunction "2_2") (pintype "bidirectional"))
      (node (ref "H23") (pin "2") (pinfunction "2_2") (pintype "bidirectional"))
      (node (ref "H25") (pin "2") (pinfunction "2_2") (pintype "bidirectional"))
      (node (ref "H3") (pin "1") (pinfunction "1_1") (pintype "bidirectional"))
      (node (ref "H3") (pin "2") (pinfunction "2_2") (pintype "bidirectional"))
      (node (ref "H3") (pin "3") (pinfunction "3_3") (pintype "bidirectional"))
      (node (ref "H3") (pin "4") (pinfunction "4_4") (pintype "bidirectional"))
      (node (ref "H30") (pin "4") (pinfunction "4_4") (pintype "bidirectional"))
      (node (ref "H31") (pin "3") (pinfunction "3_3") (pintype "bidirectional"))
      (node (ref "H6") (pin "1") (pinfunction "1_1") (pintype "bidirectional"))
      (node (ref "H6") (pin "2") (pinfunction "2_2") (pintype "bidirectional"))
      (node (ref "H6") (pin "3") (pinfunction "3_3") (pintype "bidirectional"))
      (node (ref "H6") (pin "4") (pinfunction "4_4") (pintype "bidirectional"))
      (node (ref "H9") (pin "1") (pinfunction "1_1") (pintype "bidirectional"))
      (node (ref "H9") (pin "2") (pinfunction "2_2") (pintype "bidirectional"))
      (node (ref "H9") (pin "3") (pinfunction "3_3") (pintype "bidirectional"))
      (node (ref "H9") (pin "4") (pinfunction "4_4") (pintype "bidirectional"))
      (node (ref "LED2") (pin "P$2") (pinfunction "2_P$2") (pintype "bidirectional"))
      (node (ref "Q1") (pin "1") (pinfunction "S_1") (pintype "bidirectional"))
      (node (ref "Q1") (pin "4") (pinfunction "S_4") (pintype "bidirectional"))
      (node (ref "R18") (pin "1") (pinfunction "1_1") (pintype "bidirectional"))
      (node (ref "R2") (pin "2") (pinfunction "2_2") (pintype "bidirectional"))
      (node (ref "R3") (pin "2") (pinfunction "2_2") (pintype "bidirectional"))
      (node (ref "U1") (pin "1") (pinfunction "PGND_1") (pintype "bidirectional"))
      (node (ref "U1") (pin "5") (pinfunction "FB_5") (pintype "bidirectional"))
      (node (ref "U1") (pin "6") (pinfunction "AGND_6") (pintype "bidirectional"))
      (node (ref "U1") (pin "PAD") (pinfunction "PGND_PAD") (pintype "bidirectional"))
      (node (ref "U11") (pin "GND") (pinfunction "VSS_GND") (pintype "bidirectional"))
      (node (ref "U11") (pin "GND@1") (pinfunction "VSS_GND@1") (pintype "bidirectional"))
      (node (ref "U11") (pin "GND@2") (pinfunction "VSS_GND@2") (pintype "bidirectional"))
      (node (ref "U11") (pin "SHIELD") (pinfunction "SHIELD_SHIELD") (pintype "bidirectional"))
      (node (ref "U11") (pin "SHIELD@1") (pinfunction "SHIELD_SHIELD@1") (pintype "bidirectional"))
      (node (ref "U11") (pin "SHIELD@2") (pinfunction "SHIELD_SHIELD@2") (pintype "bidirectional"))
      (node (ref "U11") (pin "SHIELD@3") (pinfunction "SHIELD_SHIELD@3") (pintype "bidirectional"))
      (node (ref "U11") (pin "VSS") (pinfunction "VSS_VSS") (pintype "bidirectional"))
      (node (ref "U13") (pin "10") (pinfunction "GND_10") (pintype "power_in"))
      (node (ref "U14") (pin "6") (pinfunction "GND_6") (pintype "bidirectional"))
      (node (ref "U14") (pin "PAD") (pinfunction "GND_PAD") (pintype "bidirectional"))
      (node (ref "U2") (pin "15") (pinfunction "A0_15") (pintype "bidirectional"))
      (node (ref "U2") (pin "16") (pinfunction "A1_16") (pintype "bidirectional"))
      (node (ref "U2") (pin "6") (pinfunction "GND_6") (pintype "bidirectional"))
      (node (ref "U2") (pin "PAD") (pinfunction "GND_PAD") (pintype "bidirectional"))
      (node (ref "U3") (pin "12") (pinfunction "GND_12") (pintype "bidirectional"))
      (node (ref "U3") (pin "2") (pinfunction "GND_2") (pintype "bidirectional"))
      (node (ref "U3") (pin "7") (pinfunction "SENSE_7") (pintype "bidirectional"))
      (node (ref "U3") (pin "PAD") (pinfunction "GND_PAD") (pintype "bidirectional"))
      (node (ref "U4") (pin "12") (pinfunction "GND_12") (pintype "bidirectional"))
      (node (ref "U4") (pin "2") (pinfunction "GND_2") (pintype "bidirectional"))
      (node (ref "U4") (pin "7") (pinfunction "SENSE_7") (pintype "bidirectional"))
      (node (ref "U4") (pin "PAD") (pinfunction "GND_PAD") (pintype "bidirectional"))
      (node (ref "U5") (pin "12") (pinfunction "GND_12") (pintype "bidirectional"))
      (node (ref "U5") (pin "2") (pinfunction "GND_2") (pintype "bidirectional"))
      (node (ref "U5") (pin "7") (pinfunction "SENSE_7") (pintype "bidirectional"))
      (node (ref "U5") (pin "PAD") (pinfunction "GND_PAD") (pintype "bidirectional"))
      (node (ref "U6") (pin "12") (pinfunction "GND_12") (pintype "bidirectional"))
      (node (ref "U6") (pin "2") (pinfunction "GND_2") (pintype "bidirectional"))
      (node (ref "U6") (pin "7") (pinfunction "SENSE_7") (pintype "bidirectional"))
      (node (ref "U6") (pin "PAD") (pinfunction "GND_PAD") (pintype "bidirectional"))
      (node (ref "U8") (pin "1") (pinfunction "CLKIN_1") (pintype "bidirectional"))
      (node (ref "U8") (pin "11") (pinfunction "FSYNC_11") (pintype "bidirectional"))
      (node (ref "U8") (pin "18") (pinfunction "GND_18") (pintype "bidirectional"))
      (node (ref "U8") (pin "9") (pinfunction "AD0_9") (pintype "bidirectional"))
      (node (ref "U9") (pin "1") (pinfunction "A1_1") (pintype "bidirectional"))
      (node (ref "U9") (pin "2") (pinfunction "A0_2") (pintype "bidirectional"))
      (node (ref "U9") (pin "7") (pinfunction "GND_7") (pintype "bidirectional"))
    )
    (net (code "65") (name "Net-(H23-Pad1)") (class "Default")
      (node (ref "H23") (pin "1") (pinfunction "1_1") (pintype "bidirectional"))
      (node (ref "J5") (pin "3") (pinfunction "3_3") (pintype "bidirectional"))
    )
    (net (code "66") (name "Net-(LED0-2)") (class "Default")
      (node (ref "LED0") (pin "P$2") (pinfunction "2_P$2") (pintype "bidirectional"))
      (node (ref "R2") (pin "1") (pinfunction "1_1") (pintype "bidirectional"))
    )
    (net (code "67") (name "Net-(LED1-2)") (class "Default")
      (node (ref "LED1") (pin "P$2") (pinfunction "2_P$2") (pintype "bidirectional"))
      (node (ref "R3") (pin "1") (pinfunction "1_1") (pintype "bidirectional"))
    )
    (net (code "68") (name "Net-(LED2-1)") (class "Default")
      (node (ref "LED2") (pin "P$1") (pinfunction "1_P$1") (pintype "bidirectional"))
      (node (ref "R4") (pin "2") (pinfunction "2_2") (pintype "bidirectional"))
    )
    (net (code "69") (name "Net-(U1-SW)") (class "Default")
      (node (ref "L1") (pin "1") (pinfunction "1_1") (pintype "passive"))
      (node (ref "U1") (pin "9") (pinfunction "SW_9") (pintype "bidirectional"))
    )
    (net (code "70") (name "Net-(U2-~{INT})") (class "Default")
      (node (ref "J21") (pin "2") (pinfunction "2_2") (pintype "bidirectional"))
      (node (ref "U2") (pin "11") (pinfunction "~{INT}_11") (pintype "bidirectional"))
    )
    (net (code "71") (name "Net-(U3-CP1)") (class "Default")
      (node (ref "C21") (pin "2") (pinfunction "2_2") (pintype "bidirectional"))
      (node (ref "U3") (pin "10") (pinfunction "CP1_10") (pintype "bidirectional"))
    )
    (net (code "72") (name "Net-(U3-CP2)") (class "Default")
      (node (ref "C21") (pin "1") (pinfunction "1_1") (pintype "bidirectional"))
      (node (ref "U3") (pin "11") (pinfunction "CP2_11") (pintype "bidirectional"))
    )
    (net (code "73") (name "Net-(U3-VCP)") (class "Default")
      (node (ref "C26") (pin "2") (pinfunction "2_2") (pintype "bidirectional"))
      (node (ref "U3") (pin "13") (pinfunction "VCP_13") (pintype "bidirectional"))
    )
    (net (code "74") (name "Net-(U4-CP1)") (class "Default")
      (node (ref "C23") (pin "2") (pinfunction "2_2") (pintype "bidirectional"))
      (node (ref "U4") (pin "10") (pinfunction "CP1_10") (pintype "bidirectional"))
    )
    (net (code "75") (name "Net-(U4-CP2)") (class "Default")
      (node (ref "C23") (pin "1") (pinfunction "1_1") (pintype "bidirectional"))
      (node (ref "U4") (pin "11") (pinfunction "CP2_11") (pintype "bidirectional"))
    )
    (net (code "76") (name "Net-(U4-VCP)") (class "Default")
      (node (ref "C27") (pin "2") (pinfunction "2_2") (pintype "bidirectional"))
      (node (ref "U4") (pin "13") (pinfunction "VCP_13") (pintype "bidirectional"))
    )
    (net (code "77") (name "Net-(U5-CP1)") (class "Default")
      (node (ref "C17") (pin "2") (pinfunction "2_2") (pintype "bidirectional"))
      (node (ref "U5") (pin "10") (pinfunction "CP1_10") (pintype "bidirectional"))
    )
    (net (code "78") (name "Net-(U5-CP2)") (class "Default")
      (node (ref "C17") (pin "1") (pinfunction "1_1") (pintype "bidirectional"))
      (node (ref "U5") (pin "11") (pinfunction "CP2_11") (pintype "bidirectional"))
    )
    (net (code "79") (name "Net-(U5-VCP)") (class "Default")
      (node (ref "C24") (pin "2") (pinfunction "2_2") (pintype "bidirectional"))
      (node (ref "U5") (pin "13") (pinfunction "VCP_13") (pintype "bidirectional"))
    )
    (net (code "80") (name "Net-(U6-CP1)") (class "Default")
      (node (ref "C19") (pin "2") (pinfunction "2_2") (pintype "bidirectional"))
      (node (ref "U6") (pin "10") (pinfunction "CP1_10") (pintype "bidirectional"))
    )
    (net (code "81") (name "Net-(U6-CP2)") (class "Default")
      (node (ref "C19") (pin "1") (pinfunction "1_1") (pintype "bidirectional"))
      (node (ref "U6") (pin "11") (pinfunction "CP2_11") (pintype "bidirectional"))
    )
    (net (code "82") (name "Net-(U6-VCP)") (class "Default")
      (node (ref "C25") (pin "2") (pinfunction "2_2") (pintype "bidirectional"))
      (node (ref "U6") (pin "13") (pinfunction "VCP_13") (pintype "bidirectional"))
    )
    (net (code "83") (name "Net-(U8-CPOUT)") (class "Default")
      (node (ref "C32") (pin "1") (pinfunction "1_1") (pintype "bidirectional"))
      (node (ref "U8") (pin "20") (pinfunction "CPOUT_20") (pintype "bidirectional"))
    )
    (net (code "84") (name "Net-(U8-REGOUT)") (class "Default")
      (node (ref "C33") (pin "2") (pinfunction "2_2") (pintype "bidirectional"))
      (node (ref "U8") (pin "10") (pinfunction "REGOUT_10") (pintype "bidirectional"))
    )
    (net (code "85") (name "Net-(U9-VIN+)") (class "Default")
      (node (ref "C1") (pin "+") (pinfunction "+_+") (pintype "passive"))
      (node (ref "D1") (pin "1") (pinfunction "1_1") (pintype "bidirectional"))
      (node (ref "H31") (pin "2") (pinfunction "2_2") (pintype "bidirectional"))
      (node (ref "R1") (pin "1") (pinfunction "1_1") (pintype "bidirectional"))
      (node (ref "U9") (pin "10") (pinfunction "VIN+_10") (pintype "bidirectional"))
    )
    (net (code "86") (name "Net-(U14-BOOT)") (class "Default")
      (node (ref "C41") (pin "1") (pinfunction "1_1") (pintype "bidirectional"))
      (node (ref "U14") (pin "1") (pinfunction "BOOT_1") (pintype "bidirectional"))
    )
    (net (code "87") (name "Net-(U14-PH)") (class "Default")
      (node (ref "C41") (pin "2") (pinfunction "2_2") (pintype "bidirectional"))
      (node (ref "D6") (pin "1") (pinfunction "1_1") (pintype "bidirectional"))
      (node (ref "L3") (pin "1") (pinfunction "1_1") (pintype "passive"))
      (node (ref "U14") (pin "8") (pinfunction "PH_8") (pintype "bidirectional"))
    )
    (net (code "88") (name "Net-(U14-VSENSE)") (class "Default")
      (node (ref "R17") (pin "1") (pinfunction "1_1") (pintype "bidirectional"))
      (node (ref "R18") (pin "2") (pinfunction "2_2") (pintype "bidirectional"))
      (node (ref "U14") (pin "4") (pinfunction "VSENSE_4") (pintype "bidirectional"))
    )
    (net (code "89") (name "VBAT") (class "Default")
      (node (ref "C2") (pin "1") (pinfunction "1_1") (pintype "bidirectional"))
      (node (ref "C42") (pin "1") (pinfunction "1_1") (pintype "bidirectional"))
      (node (ref "H31") (pin "1") (pinfunction "1_1") (pintype "bidirectional"))
      (node (ref "J1") (pin "1") (pinfunction "1_1") (pintype "bidirectional"))
      (node (ref "J11") (pin "1") (pinfunction "1_1") (pintype "bidirectional"))
      (node (ref "J14") (pin "1") (pinfunction "1_1") (pintype "bidirectional"))
      (node (ref "J17") (pin "1") (pinfunction "1_1") (pintype "bidirectional"))
      (node (ref "J20") (pin "1") (pinfunction "1_1") (pintype "bidirectional"))
      (node (ref "J4") (pin "1") (pinfunction "1_1") (pintype "bidirectional"))
      (node (ref "J5") (pin "1") (pinfunction "1_1") (pintype "bidirectional"))
      (node (ref "J8") (pin "1") (pinfunction "1_1") (pintype "bidirectional"))
      (node (ref "R1") (pin "2") (pinfunction "2_2") (pintype "bidirectional"))
      (node (ref "U1") (pin "2") (pinfunction "VIN_2") (pintype "bidirectional"))
      (node (ref "U1") (pin "3") (pinfunction "EN_3") (pintype "bidirectional"))
      (node (ref "U14") (pin "7") (pinfunction "VIN_7") (pintype "bidirectional"))
      (node (ref "U9") (pin "8") (pinfunction "VBUS_8") (pintype "bidirectional"))
      (node (ref "U9") (pin "9") (pinfunction "VIN-_9") (pintype "bidirectional"))
    )
    (net (code "90") (name "VFET") (class "Default")
      (node (ref "D3") (pin "1") (pinfunction "1_1") (pintype "bidirectional"))
      (node (ref "D4") (pin "1") (pinfunction "1_1") (pintype "bidirectional"))
      (node (ref "H19") (pin "1") (pinfunction "1_1") (pintype "bidirectional"))
      (node (ref "H19") (pin "2") (pinfunction "2_2") (pintype "bidirectional"))
      (node (ref "J5") (pin "2") (pinfunction "2_2") (pintype "bidirectional"))
    )
    (net (code "91") (name "VMOTOR") (class "Default")
      (node (ref "C10") (pin "+") (pinfunction "+_+") (pintype "passive"))
      (node (ref "C11") (pin "+") (pinfunction "+_+") (pintype "passive"))
      (node (ref "C28") (pin "1") (pinfunction "1_1") (pintype "bidirectional"))
      (node (ref "C29") (pin "1") (pinfunction "1_1") (pintype "bidirectional"))
      (node (ref "C30") (pin "1") (pinfunction "1_1") (pintype "bidirectional"))
      (node (ref "C31") (pin "1") (pinfunction "1_1") (pintype "bidirectional"))
      (node (ref "J20") (pin "2") (pinfunction "2_2") (pintype "bidirectional"))
      (node (ref "U3") (pin "8") (pinfunction "VMOT_8") (pintype "bidirectional"))
      (node (ref "U4") (pin "8") (pinfunction "VMOT_8") (pintype "bidirectional"))
      (node (ref "U5") (pin "8") (pinfunction "VMOT_8") (pintype "bidirectional"))
      (node (ref "U6") (pin "8") (pinfunction "VMOT_8") (pintype "bidirectional"))
    )
    (net (code "92") (name "unconnected-(U1-PG-Pad7)") (class "Default")
      (node (ref "U1") (pin "7") (pinfunction "PG_7") (pintype "bidirectional"))
    )
    (net (code "93") (name "unconnected-(U3-VREG-Pad14)") (class "Default")
      (node (ref "U3") (pin "14") (pinfunction "VREG_14") (pintype "bidirectional"))
    )
    (net (code "94") (name "unconnected-(U3-~{FAULT}-Pad15)") (class "Default")
      (node (ref "U3") (pin "15") (pinfunction "~{FAULT}_15") (pintype "bidirectional"))
    )
    (net (code "95") (name "unconnected-(U4-VREG-Pad14)") (class "Default")
      (node (ref "U4") (pin "14") (pinfunction "VREG_14") (pintype "bidirectional"))
    )
    (net (code "96") (name "unconnected-(U4-~{FAULT}-Pad15)") (class "Default")
      (node (ref "U4") (pin "15") (pinfunction "~{FAULT}_15") (pintype "bidirectional"))
    )
    (net (code "97") (name "unconnected-(U5-VREG-Pad14)") (class "Default")
      (node (ref "U5") (pin "14") (pinfunction "VREG_14") (pintype "bidirectional"))
    )
    (net (code "98") (name "unconnected-(U5-~{FAULT}-Pad15)") (class "Default")
      (node (ref "U5") (pin "15") (pinfunction "~{FAULT}_15") (pintype "bidirectional"))
    )
    (net (code "99") (name "unconnected-(U6-VREG-Pad14)") (class "Default")
      (node (ref "U6") (pin "14") (pinfunction "VREG_14") (pintype "bidirectional"))
    )
    (net (code "100") (name "unconnected-(U6-~{FAULT}-Pad15)") (class "Default")
      (node (ref "U6") (pin "15") (pinfunction "~{FAULT}_15") (pintype "bidirectional"))
    )
    (net (code "101") (name "unconnected-(U8-AUX_CL-Pad7)") (class "Default")
      (node (ref "U8") (pin "7") (pinfunction "AUX_CL_7") (pintype "bidirectional"))
    )
    (net (code "102") (name "unconnected-(U8-AUX_DA-Pad6)") (class "Default")
      (node (ref "U8") (pin "6") (pinfunction "AUX_DA_6") (pintype "bidirectional"))
    )
    (net (code "103") (name "unconnected-(U8-CLKOUT-Pad22)") (class "Default")
      (node (ref "U8") (pin "22") (pinfunction "CLKOUT_22") (pintype "bidirectional"))
    )
    (net (code "104") (name "unconnected-(U11-DETECT-PadCD)") (class "Default")
      (node (ref "U11") (pin "CD") (pinfunction "DETECT_CD") (pintype "bidirectional"))
    )
    (net (code "105") (name "unconnected-(U13-CTS-Pad12)") (class "Default")
      (node (ref "U13") (pin "12") (pinfunction "CTS_12") (pintype "output"))
    )
    (net (code "106") (name "unconnected-(U13-DIO0-Pad20)") (class "Default")
      (node (ref "U13") (pin "20") (pinfunction "DIO0_20") (pintype "bidirectional"))
    )
    (net (code "107") (name "unconnected-(U13-DIO1-Pad19)") (class "Default")
      (node (ref "U13") (pin "19") (pinfunction "DIO1_19") (pintype "bidirectional"))
    )
    (net (code "108") (name "unconnected-(U13-DIO2-Pad18)") (class "Default")
      (node (ref "U13") (pin "18") (pinfunction "DIO2_18") (pintype "bidirectional"))
    )
    (net (code "109") (name "unconnected-(U13-DIO3-Pad17)") (class "Default")
      (node (ref "U13") (pin "17") (pinfunction "DIO3_17") (pintype "bidirectional"))
    )
    (net (code "110") (name "unconnected-(U13-DIO4-Pad11)") (class "Default")
      (node (ref "U13") (pin "11") (pinfunction "DIO4_11") (pintype "bidirectional"))
    )
    (net (code "111") (name "unconnected-(U13-DIO5-Pad15)") (class "Default")
      (node (ref "U13") (pin "15") (pinfunction "DIO5_15") (pintype "bidirectional"))
    )
    (net (code "112") (name "unconnected-(U13-DIO11-Pad7)") (class "Default")
      (node (ref "U13") (pin "7") (pinfunction "DIO11_7") (pintype "bidirectional"))
    )
    (net (code "113") (name "unconnected-(U13-DIO12-Pad4)") (class "Default")
      (node (ref "U13") (pin "4") (pinfunction "DIO12_4") (pintype "bidirectional"))
    )
    (net (code "114") (name "unconnected-(U13-DTR-Pad9)") (class "Default")
      (node (ref "U13") (pin "9") (pinfunction "DTR_9") (pintype "bidirectional"))
    )
    (net (code "115") (name "unconnected-(U13-RES-Pad8)") (class "Default")
      (node (ref "U13") (pin "8") (pinfunction "RES_8") (pintype "bidirectional"))
    )
    (net (code "116") (name "unconnected-(U13-RES-Pad14)") (class "Default")
      (node (ref "U13") (pin "14") (pinfunction "RES_14") (pintype "bidirectional"))
    )
    (net (code "117") (name "unconnected-(U13-RESET-Pad5)") (class "Default")
      (node (ref "U13") (pin "5") (pinfunction "RESET_5") (pintype "input"))
    )
    (net (code "118") (name "unconnected-(U13-RSSI-Pad6)") (class "Default")
      (node (ref "U13") (pin "6") (pinfunction "RSSI_6") (pintype "bidirectional"))
    )
    (net (code "119") (name "unconnected-(U13-RTS-Pad16)") (class "Default")
      (node (ref "U13") (pin "16") (pinfunction "RTS_16") (pintype "input"))
    )
    (net (code "120") (name "unconnected-(U14-ENA-Pad5)") (class "Default")
      (node (ref "U14") (pin "5") (pinfunction "ENA_5") (pintype "bidirectional"))
    )
  )
)
